# ARC-S-MCU.net
KiCad netlist of a schematic drawn in Altium Designer
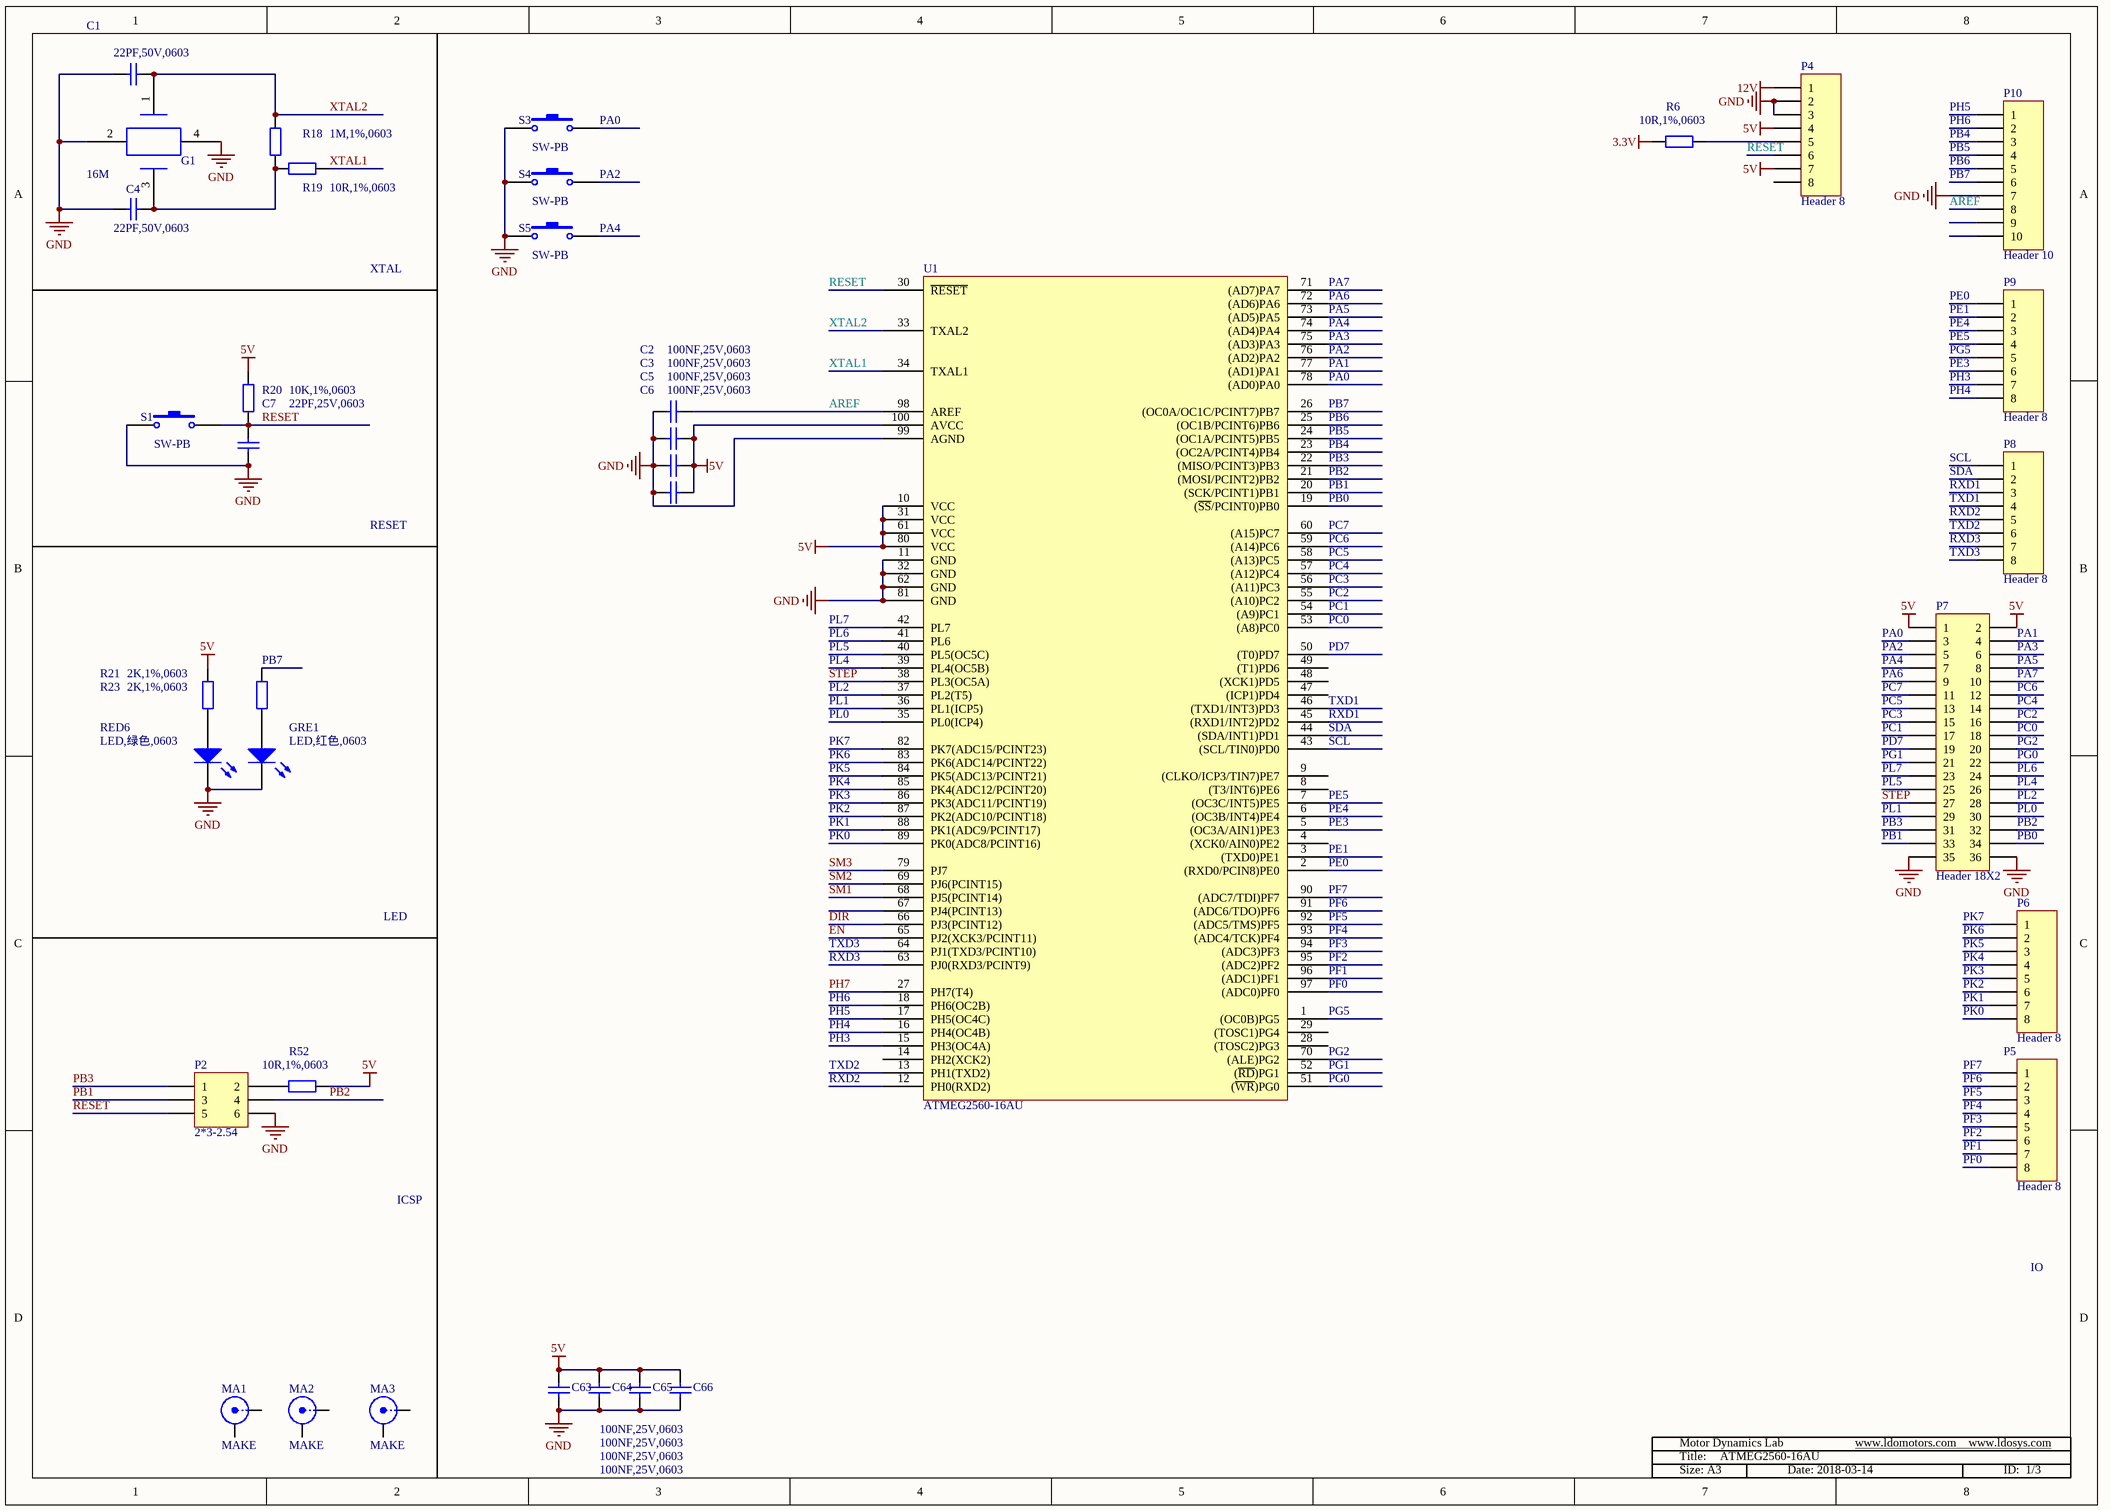
[diagram p0: ARC-S-MCU.SchDoc]

(export (version "E")
  (design (tool "Eeschema 10.0.6"))
  (components
    (comp (ref "C1")
      (value "22PF,50V,0603")
      (footprint "RC0603")
      (description "Capacitor")
      (fields (field (name "PUBLISHER") "Altium Limited"))
      (libsource (lib "Miscellaneous Devices") (part "Cap"))
    )
    (comp (ref "C2")
      (value "100NF,25V,0603")
      (footprint "RC0603")
      (description "Capacitor")
      (fields (field (name "PUBLISHER") "Altium Limited"))
      (libsource (lib "Miscellaneous Devices") (part "Cap"))
    )
    (comp (ref "C3")
      (value "100NF,25V,0603")
      (footprint "RC0603")
      (description "Capacitor")
      (fields (field (name "PUBLISHER") "Altium Limited"))
      (libsource (lib "Miscellaneous Devices") (part "Cap"))
    )
    (comp (ref "C4")
      (value "22PF,50V,0603")
      (footprint "RC0603")
      (description "Capacitor")
      (fields (field (name "PUBLISHER") "Altium Limited"))
      (libsource (lib "Miscellaneous Devices") (part "Cap"))
    )
    (comp (ref "C5")
      (value "100NF,25V,0603")
      (footprint "RC0603")
      (description "Capacitor")
      (fields (field (name "PUBLISHER") "Altium Limited"))
      (libsource (lib "Miscellaneous Devices") (part "Cap"))
    )
    (comp (ref "C6")
      (value "100NF,25V,0603")
      (footprint "RC0603")
      (description "Capacitor")
      (fields (field (name "PUBLISHER") "Altium Limited"))
      (libsource (lib "Miscellaneous Devices") (part "Cap"))
    )
    (comp (ref "C7")
      (value "22PF,25V,0603")
      (footprint "RC0603")
      (description "Capacitor")
      (fields (field (name "PUBLISHER") "Altium Limited"))
      (libsource (lib "Miscellaneous Devices") (part "Cap"))
    )
    (comp (ref "C63")
      (value "100NF,25V,0603")
      (footprint "RC0603")
      (description "Capacitor")
      (fields (field (name "PUBLISHER") "Altium Limited"))
      (libsource (lib "Miscellaneous Devices") (part "Cap"))
    )
    (comp (ref "C64")
      (value "100NF,25V,0603")
      (footprint "RC0603")
      (description "Capacitor")
      (fields (field (name "PUBLISHER") "Altium Limited"))
      (libsource (lib "Miscellaneous Devices") (part "Cap"))
    )
    (comp (ref "C65")
      (value "100NF,25V,0603")
      (footprint "RC0603")
      (description "Capacitor")
      (fields (field (name "PUBLISHER") "Altium Limited"))
      (libsource (lib "Miscellaneous Devices") (part "Cap"))
    )
    (comp (ref "C66")
      (value "100NF,25V,0603")
      (footprint "RC0603")
      (description "Capacitor")
      (fields (field (name "PUBLISHER") "Altium Limited"))
      (libsource (lib "Miscellaneous Devices") (part "Cap"))
    )
    (comp (ref "G1") (value "16M") (footprint "Y-3225") (libsource (lib "STM32F407VE") (part "G")))
    (comp (ref "GRE1")
      (value "LED,红色,0603")
      (footprint "LED-0603")
      (description "Typical INFRARED GaAs LED")
      (fields (field (name "PUBLISHER") "Altium Limited"))
      (libsource (lib "Miscellaneous Devices") (part "LED0"))
    )
    (comp (ref "MA1")
      (value "MAKE")
      (description "BNC Elbow Connector")
      (fields (field (name "PUBLISHER") "Altium Limited"))
      (libsource (lib "Miscellaneous Connectors") (part "BNC"))
    )
    (comp (ref "MA2")
      (value "MAKE")
      (description "BNC Elbow Connector")
      (fields (field (name "PUBLISHER") "Altium Limited"))
      (libsource (lib "Miscellaneous Connectors") (part "BNC"))
    )
    (comp (ref "MA3")
      (value "MAKE")
      (description "BNC Elbow Connector")
      (fields (field (name "PUBLISHER") "Altium Limited"))
      (libsource (lib "Miscellaneous Connectors") (part "BNC"))
    )
    (comp (ref "P2")
      (value "2*3-2.54")
      (footprint "HDR2X3")
      (description "Header, 3-Pin, Dual row")
      (fields (field (name "PUBLISHER") "Altium Limited"))
      (libsource (lib "Miscellaneous Connectors") (part "Header 3X2"))
    )
    (comp (ref "P4")
      (value "Header 8")
      (footprint "HDR1X8")
      (description "Header, 8-Pin")
      (fields (field (name "PUBLISHER") "Altium Limited"))
      (libsource (lib "Miscellaneous Connectors") (part "Header 8"))
    )
    (comp (ref "P5")
      (value "Header 8")
      (footprint "HDR1X8")
      (description "Header, 8-Pin")
      (fields (field (name "PUBLISHER") "Altium Limited"))
      (libsource (lib "Miscellaneous Connectors") (part "Header 8"))
    )
    (comp (ref "P6")
      (value "Header 8")
      (footprint "HDR1X8")
      (description "Header, 8-Pin")
      (fields (field (name "PUBLISHER") "Altium Limited"))
      (libsource (lib "Miscellaneous Connectors") (part "Header 8"))
    )
    (comp (ref "P7")
      (value "Header 18X2")
      (footprint "HDR2X18")
      (description "Header, 18-Pin, Dual row")
      (fields (field (name "PUBLISHER") "Altium Limited"))
      (libsource (lib "Miscellaneous Connectors") (part "Header 18X2"))
    )
    (comp (ref "P8")
      (value "Header 8")
      (footprint "HDR1X8")
      (description "Header, 8-Pin")
      (fields (field (name "PUBLISHER") "Altium Limited"))
      (libsource (lib "Miscellaneous Connectors") (part "Header 8"))
    )
    (comp (ref "P9")
      (value "Header 8")
      (footprint "HDR1X8")
      (description "Header, 8-Pin")
      (fields (field (name "PUBLISHER") "Altium Limited"))
      (libsource (lib "Miscellaneous Connectors") (part "Header 8"))
    )
    (comp (ref "P10")
      (value "Header 10")
      (footprint "HDR1X10")
      (description "Header, 10-Pin")
      (fields (field (name "PUBLISHER") "Altium Limited"))
      (libsource (lib "Miscellaneous Connectors") (part "Header 10"))
    )
    (comp (ref "R6")
      (value "10R,1%,0603")
      (footprint "RC0603")
      (description "Resistor")
      (fields (field (name "PUBLISHER") "Altium Limited"))
      (libsource (lib "") (part "Res2_2"))
    )
    (comp (ref "R18")
      (value "1M,1%,0603")
      (footprint "RC0603")
      (description "Resistor")
      (fields (field (name "PUBLISHER") "Altium Limited"))
      (libsource (lib "") (part "Res2_1"))
    )
    (comp (ref "R19")
      (value "10R,1%,0603")
      (footprint "RC0603")
      (description "Resistor")
      (fields (field (name "PUBLISHER") "Altium Limited"))
      (libsource (lib "Miscellaneous Devices") (part "Res2"))
    )
    (comp (ref "R20")
      (value "10K,1%,0603")
      (footprint "RC0603")
      (description "Resistor")
      (fields (field (name "PUBLISHER") "Altium Limited"))
      (libsource (lib "") (part "Res2_1"))
    )
    (comp (ref "R21")
      (value "2K,1%,0603")
      (footprint "RC0603")
      (description "Resistor")
      (fields (field (name "PUBLISHER") "Altium Limited"))
      (libsource (lib "") (part "Res2_1"))
    )
    (comp (ref "R23")
      (value "2K,1%,0603")
      (footprint "RC0603")
      (description "Resistor")
      (fields (field (name "PUBLISHER") "Altium Limited"))
      (libsource (lib "") (part "Res2_1"))
    )
    (comp (ref "R52")
      (value "10R,1%,0603")
      (footprint "RC0603")
      (description "Resistor")
      (fields (field (name "PUBLISHER") "Altium Limited"))
      (libsource (lib "") (part "Res2_2"))
    )
    (comp (ref "RED6")
      (value "LED,绿色,0603")
      (footprint "LED-0603")
      (description "Typical INFRARED GaAs LED")
      (fields (field (name "PUBLISHER") "Altium Limited"))
      (libsource (lib "Miscellaneous Devices") (part "LED0"))
    )
    (comp (ref "S1")
      (value "SW-PB")
      (footprint "DIP6*6")
      (description "Switch")
      (fields (field (name "PUBLISHER") "Altium Limited"))
      (libsource (lib "Miscellaneous Devices") (part "SW-PB"))
    )
    (comp (ref "S3")
      (value "SW-PB")
      (footprint "DIP6*6")
      (description "Switch")
      (fields (field (name "PUBLISHER") "Altium Limited"))
      (libsource (lib "Miscellaneous Devices") (part "SW-PB"))
    )
    (comp (ref "S4")
      (value "SW-PB")
      (footprint "DIP6*6")
      (description "Switch")
      (fields (field (name "PUBLISHER") "Altium Limited"))
      (libsource (lib "Miscellaneous Devices") (part "SW-PB"))
    )
    (comp (ref "S5")
      (value "SW-PB")
      (footprint "DIP6*6")
      (description "Switch")
      (fields (field (name "PUBLISHER") "Altium Limited"))
      (libsource (lib "Miscellaneous Devices") (part "SW-PB"))
    )
    (comp (ref "U1")
      (value "ATMEG2560-16AU")
      (footprint "LQFP-100")
      (libsource (lib "LDO原理图库") (part "ATMEG2560-16AU"))
    )
  )
  (nets
    (net (code "1") (name "/AREF") (class "Default")
      (node (ref "C2") (pin "1") (pinfunction "1_1") (pintype "passive"))
      (node (ref "P10") (pin "8") (pinfunction "8_8") (pintype "passive"))
      (node (ref "U1") (pin "98") (pinfunction "AREF_98") (pintype "passive"))
    )
    (net (code "2") (name "/DIR") (class "Default")
      (node (ref "U1") (pin "66") (pinfunction "PJ3(PCINT12)_66") (pintype "passive"))
    )
    (net (code "3") (name "/EN") (class "Default")
      (node (ref "U1") (pin "65") (pinfunction "PJ2(XCK3/PCINT11)_65") (pintype "passive"))
    )
    (net (code "4") (name "/PA0") (class "Default")
      (node (ref "P7") (pin "3") (pinfunction "3_3") (pintype "passive"))
      (node (ref "S3") (pin "2") (pinfunction "2_2") (pintype "passive"))
      (node (ref "U1") (pin "78") (pinfunction "(AD0)PA0_78") (pintype "passive"))
    )
    (net (code "5") (name "/PA1") (class "Default")
      (node (ref "P7") (pin "4") (pinfunction "4_4") (pintype "passive"))
      (node (ref "U1") (pin "77") (pinfunction "(AD1)PA1_77") (pintype "passive"))
    )
    (net (code "6") (name "/PA2") (class "Default")
      (node (ref "P7") (pin "5") (pinfunction "5_5") (pintype "passive"))
      (node (ref "S4") (pin "2") (pinfunction "2_2") (pintype "passive"))
      (node (ref "U1") (pin "76") (pinfunction "(AD2)PA2_76") (pintype "passive"))
    )
    (net (code "7") (name "/PA3") (class "Default")
      (node (ref "P7") (pin "6") (pinfunction "6_6") (pintype "passive"))
      (node (ref "U1") (pin "75") (pinfunction "(AD3)PA3_75") (pintype "passive"))
    )
    (net (code "8") (name "/PA4") (class "Default")
      (node (ref "P7") (pin "7") (pinfunction "7_7") (pintype "passive"))
      (node (ref "S5") (pin "2") (pinfunction "2_2") (pintype "passive"))
      (node (ref "U1") (pin "74") (pinfunction "(AD4)PA4_74") (pintype "passive"))
    )
    (net (code "9") (name "/PA5") (class "Default")
      (node (ref "P7") (pin "8") (pinfunction "8_8") (pintype "passive"))
      (node (ref "U1") (pin "73") (pinfunction "(AD5)PA5_73") (pintype "passive"))
    )
    (net (code "10") (name "/PA6") (class "Default")
      (node (ref "P7") (pin "9") (pinfunction "9_9") (pintype "passive"))
      (node (ref "U1") (pin "72") (pinfunction "(AD6)PA6_72") (pintype "passive"))
    )
    (net (code "11") (name "/PA7") (class "Default")
      (node (ref "P7") (pin "10") (pinfunction "10_10") (pintype "passive"))
      (node (ref "U1") (pin "71") (pinfunction "(AD7)PA7_71") (pintype "passive"))
    )
    (net (code "12") (name "/PB0") (class "Default")
      (node (ref "P7") (pin "34") (pinfunction "34_34") (pintype "passive"))
      (node (ref "U1") (pin "19") (pinfunction "(~{SS}/PCINT0)PB0_19") (pintype "passive"))
    )
    (net (code "13") (name "/PB1") (class "Default")
      (node (ref "P2") (pin "3") (pinfunction "3_3") (pintype "passive"))
      (node (ref "P7") (pin "33") (pinfunction "33_33") (pintype "passive"))
      (node (ref "U1") (pin "20") (pinfunction "(SCK/PCINT1)PB1_20") (pintype "passive"))
    )
    (net (code "14") (name "/PB2") (class "Default")
      (node (ref "P2") (pin "4") (pinfunction "4_4") (pintype "passive"))
      (node (ref "P7") (pin "32") (pinfunction "32_32") (pintype "passive"))
      (node (ref "U1") (pin "21") (pinfunction "(MOSI/PCINT2)PB2_21") (pintype "passive"))
    )
    (net (code "15") (name "/PB3") (class "Default")
      (node (ref "P2") (pin "1") (pinfunction "1_1") (pintype "passive"))
      (node (ref "P7") (pin "31") (pinfunction "31_31") (pintype "passive"))
      (node (ref "U1") (pin "22") (pinfunction "(MISO/PCINT3)PB3_22") (pintype "passive"))
    )
    (net (code "16") (name "/PB4") (class "Default")
      (node (ref "P10") (pin "3") (pinfunction "3_3") (pintype "passive"))
      (node (ref "U1") (pin "23") (pinfunction "(OC2A/PCINT4)PB4_23") (pintype "passive"))
    )
    (net (code "17") (name "/PB5") (class "Default")
      (node (ref "P10") (pin "4") (pinfunction "4_4") (pintype "passive"))
      (node (ref "U1") (pin "24") (pinfunction "(OC1A/PCINT5)PB5_24") (pintype "passive"))
    )
    (net (code "18") (name "/PB6") (class "Default")
      (node (ref "P10") (pin "5") (pinfunction "5_5") (pintype "passive"))
      (node (ref "U1") (pin "25") (pinfunction "(OC1B/PCINT6)PB6_25") (pintype "passive"))
    )
    (net (code "19") (name "/PB7") (class "Default")
      (node (ref "P10") (pin "6") (pinfunction "6_6") (pintype "passive"))
      (node (ref "R21") (pin "1") (pinfunction "1_1") (pintype "passive"))
      (node (ref "U1") (pin "26") (pinfunction "(OC0A/OC1C/PCINT7)PB7_26") (pintype "passive"))
    )
    (net (code "20") (name "/PC0") (class "Default")
      (node (ref "P7") (pin "18") (pinfunction "18_18") (pintype "passive"))
      (node (ref "U1") (pin "53") (pinfunction "(A8)PC0_53") (pintype "passive"))
    )
    (net (code "21") (name "/PC1") (class "Default")
      (node (ref "P7") (pin "17") (pinfunction "17_17") (pintype "passive"))
      (node (ref "U1") (pin "54") (pinfunction "(A9)PC1_54") (pintype "passive"))
    )
    (net (code "22") (name "/PC2") (class "Default")
      (node (ref "P7") (pin "16") (pinfunction "16_16") (pintype "passive"))
      (node (ref "U1") (pin "55") (pinfunction "(A10)PC2_55") (pintype "passive"))
    )
    (net (code "23") (name "/PC3") (class "Default")
      (node (ref "P7") (pin "15") (pinfunction "15_15") (pintype "passive"))
      (node (ref "U1") (pin "56") (pinfunction "(A11)PC3_56") (pintype "passive"))
    )
    (net (code "24") (name "/PC4") (class "Default")
      (node (ref "P7") (pin "14") (pinfunction "14_14") (pintype "passive"))
      (node (ref "U1") (pin "57") (pinfunction "(A12)PC4_57") (pintype "passive"))
    )
    (net (code "25") (name "/PC5") (class "Default")
      (node (ref "P7") (pin "13") (pinfunction "13_13") (pintype "passive"))
      (node (ref "U1") (pin "58") (pinfunction "(A13)PC5_58") (pintype "passive"))
    )
    (net (code "26") (name "/PC6") (class "Default")
      (node (ref "P7") (pin "12") (pinfunction "12_12") (pintype "passive"))
      (node (ref "U1") (pin "59") (pinfunction "(A14)PC6_59") (pintype "passive"))
    )
    (net (code "27") (name "/PC7") (class "Default")
      (node (ref "P7") (pin "11") (pinfunction "11_11") (pintype "passive"))
      (node (ref "U1") (pin "60") (pinfunction "(A15)PC7_60") (pintype "passive"))
    )
    (net (code "28") (name "/PD7") (class "Default")
      (node (ref "P7") (pin "19") (pinfunction "19_19") (pintype "passive"))
      (node (ref "U1") (pin "50") (pinfunction "(T0)PD7_50") (pintype "passive"))
    )
    (net (code "29") (name "/PE0") (class "Default")
      (node (ref "P9") (pin "1") (pinfunction "1_1") (pintype "passive"))
      (node (ref "U1") (pin "2") (pinfunction "(RXD0/PCIN8)PE0_2") (pintype "passive"))
    )
    (net (code "30") (name "/PE1") (class "Default")
      (node (ref "P9") (pin "2") (pinfunction "2_2") (pintype "passive"))
      (node (ref "U1") (pin "3") (pinfunction "(TXD0)PE1_3") (pintype "passive"))
    )
    (net (code "31") (name "/PE3") (class "Default")
      (node (ref "P9") (pin "6") (pinfunction "6_6") (pintype "passive"))
      (node (ref "U1") (pin "5") (pinfunction "(OC3A/AIN1)PE3_5") (pintype "passive"))
    )
    (net (code "32") (name "/PE4") (class "Default")
      (node (ref "P9") (pin "3") (pinfunction "3_3") (pintype "passive"))
      (node (ref "U1") (pin "6") (pinfunction "(OC3B/INT4)PE4_6") (pintype "passive"))
    )
    (net (code "33") (name "/PE5") (class "Default")
      (node (ref "P9") (pin "4") (pinfunction "4_4") (pintype "passive"))
      (node (ref "U1") (pin "7") (pinfunction "(OC3C/INT5)PE5_7") (pintype "passive"))
    )
    (net (code "34") (name "/PF0") (class "Default")
      (node (ref "P5") (pin "8") (pinfunction "8_8") (pintype "passive"))
      (node (ref "U1") (pin "97") (pinfunction "(ADC0)PF0_97") (pintype "passive"))
    )
    (net (code "35") (name "/PF1") (class "Default")
      (node (ref "P5") (pin "7") (pinfunction "7_7") (pintype "passive"))
      (node (ref "U1") (pin "96") (pinfunction "(ADC1)PF1_96") (pintype "passive"))
    )
    (net (code "36") (name "/PF2") (class "Default")
      (node (ref "P5") (pin "6") (pinfunction "6_6") (pintype "passive"))
      (node (ref "U1") (pin "95") (pinfunction "(ADC2)PF2_95") (pintype "passive"))
    )
    (net (code "37") (name "/PF3") (class "Default")
      (node (ref "P5") (pin "5") (pinfunction "5_5") (pintype "passive"))
      (node (ref "U1") (pin "94") (pinfunction "(ADC3)PF3_94") (pintype "passive"))
    )
    (net (code "38") (name "/PF4") (class "Default")
      (node (ref "P5") (pin "4") (pinfunction "4_4") (pintype "passive"))
      (node (ref "U1") (pin "93") (pinfunction "(ADC4/TCK)PF4_93") (pintype "passive"))
    )
    (net (code "39") (name "/PF5") (class "Default")
      (node (ref "P5") (pin "3") (pinfunction "3_3") (pintype "passive"))
      (node (ref "U1") (pin "92") (pinfunction "(ADC5/TMS)PF5_92") (pintype "passive"))
    )
    (net (code "40") (name "/PF6") (class "Default")
      (node (ref "P5") (pin "2") (pinfunction "2_2") (pintype "passive"))
      (node (ref "U1") (pin "91") (pinfunction "(ADC6/TDO)PF6_91") (pintype "passive"))
    )
    (net (code "41") (name "/PF7") (class "Default")
      (node (ref "P5") (pin "1") (pinfunction "1_1") (pintype "passive"))
      (node (ref "U1") (pin "90") (pinfunction "(ADC7/TDI)PF7_90") (pintype "passive"))
    )
    (net (code "42") (name "/PG0") (class "Default")
      (node (ref "P7") (pin "22") (pinfunction "22_22") (pintype "passive"))
      (node (ref "U1") (pin "51") (pinfunction "(~{WR})PG0_51") (pintype "passive"))
    )
    (net (code "43") (name "/PG1") (class "Default")
      (node (ref "P7") (pin "21") (pinfunction "21_21") (pintype "passive"))
      (node (ref "U1") (pin "52") (pinfunction "(~{RD})PG1_52") (pintype "passive"))
    )
    (net (code "44") (name "/PG2") (class "Default")
      (node (ref "P7") (pin "20") (pinfunction "20_20") (pintype "passive"))
      (node (ref "U1") (pin "70") (pinfunction "(ALE)PG2_70") (pintype "passive"))
    )
    (net (code "45") (name "/PG5") (class "Default")
      (node (ref "P9") (pin "5") (pinfunction "5_5") (pintype "passive"))
      (node (ref "U1") (pin "1") (pinfunction "(OC0B)PG5_1") (pintype "passive"))
    )
    (net (code "46") (name "/PH3") (class "Default")
      (node (ref "P9") (pin "7") (pinfunction "7_7") (pintype "passive"))
      (node (ref "U1") (pin "15") (pinfunction "PH3(OC4A)_15") (pintype "passive"))
    )
    (net (code "47") (name "/PH4") (class "Default")
      (node (ref "P9") (pin "8") (pinfunction "8_8") (pintype "passive"))
      (node (ref "U1") (pin "16") (pinfunction "PH4(OC4B)_16") (pintype "passive"))
    )
    (net (code "48") (name "/PH5") (class "Default")
      (node (ref "P10") (pin "1") (pinfunction "1_1") (pintype "passive"))
      (node (ref "U1") (pin "17") (pinfunction "PH5(OC4C)_17") (pintype "passive"))
    )
    (net (code "49") (name "/PH6") (class "Default")
      (node (ref "P10") (pin "2") (pinfunction "2_2") (pintype "passive"))
      (node (ref "U1") (pin "18") (pinfunction "PH6(OC2B)_18") (pintype "passive"))
    )
    (net (code "50") (name "/PH7") (class "Default")
      (node (ref "U1") (pin "27") (pinfunction "PH7(T4)_27") (pintype "passive"))
    )
    (net (code "51") (name "/PK0") (class "Default")
      (node (ref "P6") (pin "8") (pinfunction "8_8") (pintype "passive"))
      (node (ref "U1") (pin "89") (pinfunction "PK0(ADC8/PCINT16)_89") (pintype "passive"))
    )
    (net (code "52") (name "/PK1") (class "Default")
      (node (ref "P6") (pin "7") (pinfunction "7_7") (pintype "passive"))
      (node (ref "U1") (pin "88") (pinfunction "PK1(ADC9/PCINT17)_88") (pintype "passive"))
    )
    (net (code "53") (name "/PK2") (class "Default")
      (node (ref "P6") (pin "6") (pinfunction "6_6") (pintype "passive"))
      (node (ref "U1") (pin "87") (pinfunction "PK2(ADC10/PCINT18)_87") (pintype "passive"))
    )
    (net (code "54") (name "/PK3") (class "Default")
      (node (ref "P6") (pin "5") (pinfunction "5_5") (pintype "passive"))
      (node (ref "U1") (pin "86") (pinfunction "PK3(ADC11/PCINT19)_86") (pintype "passive"))
    )
    (net (code "55") (name "/PK4") (class "Default")
      (node (ref "P6") (pin "4") (pinfunction "4_4") (pintype "passive"))
      (node (ref "U1") (pin "85") (pinfunction "PK4(ADC12/PCINT20)_85") (pintype "passive"))
    )
    (net (code "56") (name "/PK5") (class "Default")
      (node (ref "P6") (pin "3") (pinfunction "3_3") (pintype "passive"))
      (node (ref "U1") (pin "84") (pinfunction "PK5(ADC13/PCINT21)_84") (pintype "passive"))
    )
    (net (code "57") (name "/PK6") (class "Default")
      (node (ref "P6") (pin "2") (pinfunction "2_2") (pintype "passive"))
      (node (ref "U1") (pin "83") (pinfunction "PK6(ADC14/PCINT22)_83") (pintype "passive"))
    )
    (net (code "58") (name "/PK7") (class "Default")
      (node (ref "P6") (pin "1") (pinfunction "1_1") (pintype "passive"))
      (node (ref "U1") (pin "82") (pinfunction "PK7(ADC15/PCINT23)_82") (pintype "passive"))
    )
    (net (code "59") (name "/PL0") (class "Default")
      (node (ref "P7") (pin "30") (pinfunction "30_30") (pintype "passive"))
      (node (ref "U1") (pin "35") (pinfunction "PL0(ICP4)_35") (pintype "passive"))
    )
    (net (code "60") (name "/PL1") (class "Default")
      (node (ref "P7") (pin "29") (pinfunction "29_29") (pintype "passive"))
      (node (ref "U1") (pin "36") (pinfunction "PL1(ICP5)_36") (pintype "passive"))
    )
    (net (code "61") (name "/PL2") (class "Default")
      (node (ref "P7") (pin "28") (pinfunction "28_28") (pintype "passive"))
      (node (ref "U1") (pin "37") (pinfunction "PL2(T5)_37") (pintype "passive"))
    )
    (net (code "62") (name "/PL4") (class "Default")
      (node (ref "P7") (pin "26") (pinfunction "26_26") (pintype "passive"))
      (node (ref "U1") (pin "39") (pinfunction "PL4(OC5B)_39") (pintype "passive"))
    )
    (net (code "63") (name "/PL5") (class "Default")
      (node (ref "P7") (pin "25") (pinfunction "25_25") (pintype "passive"))
      (node (ref "U1") (pin "40") (pinfunction "PL5(OC5C)_40") (pintype "passive"))
    )
    (net (code "64") (name "/PL6") (class "Default")
      (node (ref "P7") (pin "24") (pinfunction "24_24") (pintype "passive"))
      (node (ref "U1") (pin "41") (pinfunction "PL6_41") (pintype "passive"))
    )
    (net (code "65") (name "/PL7") (class "Default")
      (node (ref "P7") (pin "23") (pinfunction "23_23") (pintype "passive"))
      (node (ref "U1") (pin "42") (pinfunction "PL7_42") (pintype "passive"))
    )
    (net (code "66") (name "/RESET") (class "Default")
      (node (ref "C7") (pin "1") (pinfunction "1_1") (pintype "passive"))
      (node (ref "P2") (pin "5") (pinfunction "5_5") (pintype "passive"))
      (node (ref "P4") (pin "6") (pinfunction "6_6") (pintype "passive"))
      (node (ref "R20") (pin "2") (pinfunction "2_2") (pintype "passive"))
      (node (ref "S1") (pin "2") (pinfunction "2_2") (pintype "passive"))
      (node (ref "U1") (pin "30") (pinfunction "~{RESET}_30") (pintype "passive"))
    )
    (net (code "67") (name "/RXD1") (class "Default")
      (node (ref "P8") (pin "3") (pinfunction "3_3") (pintype "passive"))
      (node (ref "U1") (pin "45") (pinfunction "(RXD1/INT2)PD2_45") (pintype "passive"))
    )
    (net (code "68") (name "/RXD2") (class "Default")
      (node (ref "P8") (pin "5") (pinfunction "5_5") (pintype "passive"))
      (node (ref "U1") (pin "12") (pinfunction "PH0(RXD2)_12") (pintype "passive"))
    )
    (net (code "69") (name "/RXD3") (class "Default")
      (node (ref "P8") (pin "7") (pinfunction "7_7") (pintype "passive"))
      (node (ref "U1") (pin "63") (pinfunction "PJ0(RXD3/PCINT9)_63") (pintype "passive"))
    )
    (net (code "70") (name "/SCL") (class "Default")
      (node (ref "P8") (pin "1") (pinfunction "1_1") (pintype "passive"))
      (node (ref "U1") (pin "43") (pinfunction "(SCL/TIN0)PD0_43") (pintype "passive"))
    )
    (net (code "71") (name "/SDA") (class "Default")
      (node (ref "P8") (pin "2") (pinfunction "2_2") (pintype "passive"))
      (node (ref "U1") (pin "44") (pinfunction "(SDA/INT1)PD1_44") (pintype "passive"))
    )
    (net (code "72") (name "/SM1") (class "Default")
      (node (ref "U1") (pin "68") (pinfunction "PJ5(PCINT14)_68") (pintype "passive"))
    )
    (net (code "73") (name "/SM2") (class "Default")
      (node (ref "U1") (pin "69") (pinfunction "PJ6(PCINT15)_69") (pintype "passive"))
    )
    (net (code "74") (name "/SM3") (class "Default")
      (node (ref "U1") (pin "79") (pinfunction "PJ7_79") (pintype "passive"))
    )
    (net (code "75") (name "/STEP") (class "Default")
      (node (ref "P7") (pin "27") (pinfunction "27_27") (pintype "passive"))
      (node (ref "U1") (pin "38") (pinfunction "PL3(OC5A)_38") (pintype "passive"))
    )
    (net (code "76") (name "/TXD1") (class "Default")
      (node (ref "P8") (pin "4") (pinfunction "4_4") (pintype "passive"))
      (node (ref "U1") (pin "46") (pinfunction "(TXD1/INT3)PD3_46") (pintype "passive"))
    )
    (net (code "77") (name "/TXD2") (class "Default")
      (node (ref "P8") (pin "6") (pinfunction "6_6") (pintype "passive"))
      (node (ref "U1") (pin "13") (pinfunction "PH1(TXD2)_13") (pintype "passive"))
    )
    (net (code "78") (name "/TXD3") (class "Default")
      (node (ref "P8") (pin "8") (pinfunction "8_8") (pintype "passive"))
      (node (ref "U1") (pin "64") (pinfunction "PJ1(TXD3/PCINT10)_64") (pintype "passive"))
    )
    (net (code "79") (name "/XTAL1") (class "Default")
      (node (ref "R19") (pin "2") (pinfunction "2_2") (pintype "passive"))
      (node (ref "U1") (pin "34") (pinfunction "TXAL1_34") (pintype "passive"))
    )
    (net (code "80") (name "/XTAL2") (class "Default")
      (node (ref "C1") (pin "1") (pinfunction "1_1") (pintype "passive"))
      (node (ref "G1") (pin "1") (pintype "passive"))
      (node (ref "R18") (pin "1") (pinfunction "1_1") (pintype "passive"))
      (node (ref "U1") (pin "33") (pinfunction "TXAL2_33") (pintype "passive"))
    )
    (net (code "81") (name "3.3V") (class "Default")
      (node (ref "R6") (pin "2") (pinfunction "2_2") (pintype "passive"))
    )
    (net (code "82") (name "5V") (class "Default")
      (node (ref "C3") (pin "1") (pinfunction "1_1") (pintype "passive"))
      (node (ref "C5") (pin "1") (pinfunction "1_1") (pintype "passive"))
      (node (ref "C6") (pin "1") (pinfunction "1_1") (pintype "passive"))
      (node (ref "C63") (pin "1") (pinfunction "1_1") (pintype "passive"))
      (node (ref "C64") (pin "1") (pinfunction "1_1") (pintype "passive"))
      (node (ref "C65") (pin "1") (pinfunction "1_1") (pintype "passive"))
      (node (ref "C66") (pin "1") (pinfunction "1_1") (pintype "passive"))
      (node (ref "P4") (pin "4") (pinfunction "4_4") (pintype "passive"))
      (node (ref "P4") (pin "7") (pinfunction "7_7") (pintype "passive"))
      (node (ref "P7") (pin "1") (pinfunction "1_1") (pintype "passive"))
      (node (ref "P7") (pin "2") (pinfunction "2_2") (pintype "passive"))
      (node (ref "R20") (pin "1") (pinfunction "1_1") (pintype "passive"))
      (node (ref "R23") (pin "1") (pinfunction "1_1") (pintype "passive"))
      (node (ref "R52") (pin "1") (pinfunction "1_1") (pintype "passive"))
      (node (ref "U1") (pin "10") (pinfunction "VCC_10") (pintype "passive"))
      (node (ref "U1") (pin "100") (pinfunction "AVCC_100") (pintype "passive"))
      (node (ref "U1") (pin "31") (pinfunction "VCC_31") (pintype "passive"))
      (node (ref "U1") (pin "61") (pinfunction "VCC_61") (pintype "passive"))
      (node (ref "U1") (pin "80") (pinfunction "VCC_80") (pintype "passive"))
    )
    (net (code "83") (name "12V") (class "Default")
      (node (ref "P4") (pin "1") (pinfunction "1_1") (pintype "passive"))
    )
    (net (code "84") (name "GND") (class "Default")
      (node (ref "C1") (pin "2") (pinfunction "2_2") (pintype "passive"))
      (node (ref "C2") (pin "2") (pinfunction "2_2") (pintype "passive"))
      (node (ref "C3") (pin "2") (pinfunction "2_2") (pintype "passive"))
      (node (ref "C4") (pin "1") (pinfunction "1_1") (pintype "passive"))
      (node (ref "C5") (pin "2") (pinfunction "2_2") (pintype "passive"))
      (node (ref "C6") (pin "2") (pinfunction "2_2") (pintype "passive"))
      (node (ref "C63") (pin "2") (pinfunction "2_2") (pintype "passive"))
      (node (ref "C64") (pin "2") (pinfunction "2_2") (pintype "passive"))
      (node (ref "C65") (pin "2") (pinfunction "2_2") (pintype "passive"))
      (node (ref "C66") (pin "2") (pinfunction "2_2") (pintype "passive"))
      (node (ref "C7") (pin "2") (pinfunction "2_2") (pintype "passive"))
      (node (ref "G1") (pin "2") (pintype "passive"))
      (node (ref "G1") (pin "4") (pintype "passive"))
      (node (ref "GRE1") (pin "2") (pinfunction "K_2") (pintype "passive"))
      (node (ref "P10") (pin "7") (pinfunction "7_7") (pintype "passive"))
      (node (ref "P2") (pin "6") (pinfunction "6_6") (pintype "passive"))
      (node (ref "P4") (pin "2") (pinfunction "2_2") (pintype "passive"))
      (node (ref "P4") (pin "3") (pinfunction "3_3") (pintype "passive"))
      (node (ref "P7") (pin "35") (pinfunction "35_35") (pintype "passive"))
      (node (ref "P7") (pin "36") (pinfunction "36_36") (pintype "passive"))
      (node (ref "RED6") (pin "2") (pinfunction "K_2") (pintype "passive"))
      (node (ref "S1") (pin "1") (pinfunction "1_1") (pintype "passive"))
      (node (ref "S3") (pin "1") (pinfunction "1_1") (pintype "passive"))
      (node (ref "S4") (pin "1") (pinfunction "1_1") (pintype "passive"))
      (node (ref "S5") (pin "1") (pinfunction "1_1") (pintype "passive"))
      (node (ref "U1") (pin "11") (pinfunction "GND_11") (pintype "passive"))
      (node (ref "U1") (pin "32") (pinfunction "GND_32") (pintype "passive"))
      (node (ref "U1") (pin "62") (pinfunction "GND_62") (pintype "passive"))
      (node (ref "U1") (pin "81") (pinfunction "GND_81") (pintype "passive"))
      (node (ref "U1") (pin "99") (pinfunction "AGND_99") (pintype "passive"))
    )
    (net (code "85") (name "Net-(C4-Pad2)") (class "Default")
      (node (ref "C4") (pin "2") (pinfunction "2_2") (pintype "passive"))
      (node (ref "G1") (pin "3") (pintype "passive"))
      (node (ref "R18") (pin "2") (pinfunction "2_2") (pintype "passive"))
      (node (ref "R19") (pin "1") (pinfunction "1_1") (pintype "passive"))
    )
    (net (code "86") (name "Net-(GRE1-A)") (class "Default")
      (node (ref "GRE1") (pin "1") (pinfunction "A_1") (pintype "passive"))
      (node (ref "R21") (pin "2") (pinfunction "2_2") (pintype "passive"))
    )
    (net (code "87") (name "Net-(P2-Pad2)") (class "Default")
      (node (ref "P2") (pin "2") (pinfunction "2_2") (pintype "passive"))
      (node (ref "R52") (pin "2") (pinfunction "2_2") (pintype "passive"))
    )
    (net (code "88") (name "Net-(P4-Pad5)") (class "Default")
      (node (ref "P4") (pin "5") (pinfunction "5_5") (pintype "passive"))
      (node (ref "R6") (pin "1") (pinfunction "1_1") (pintype "passive"))
    )
    (net (code "89") (name "Net-(RED6-A)") (class "Default")
      (node (ref "R23") (pin "2") (pinfunction "2_2") (pintype "passive"))
      (node (ref "RED6") (pin "1") (pinfunction "A_1") (pintype "passive"))
    )
    (net (code "90") (name "unconnected-(MA1-X-Pad1)") (class "Default")
      (node (ref "MA1") (pin "1") (pinfunction "X_1") (pintype "passive"))
    )
    (net (code "91") (name "unconnected-(MA1-Y-Pad2)") (class "Default")
      (node (ref "MA1") (pin "2") (pinfunction "Y_2") (pintype "passive"))
    )
    (net (code "92") (name "unconnected-(MA2-X-Pad1)") (class "Default")
      (node (ref "MA2") (pin "1") (pinfunction "X_1") (pintype "passive"))
    )
    (net (code "93") (name "unconnected-(MA2-Y-Pad2)") (class "Default")
      (node (ref "MA2") (pin "2") (pinfunction "Y_2") (pintype "passive"))
    )
    (net (code "94") (name "unconnected-(MA3-X-Pad1)") (class "Default")
      (node (ref "MA3") (pin "1") (pinfunction "X_1") (pintype "passive"))
    )
    (net (code "95") (name "unconnected-(MA3-Y-Pad2)") (class "Default")
      (node (ref "MA3") (pin "2") (pinfunction "Y_2") (pintype "passive"))
    )
    (net (code "96") (name "unconnected-(P4-Pad8)") (class "Default")
      (node (ref "P4") (pin "8") (pinfunction "8_8") (pintype "passive"))
    )
    (net (code "97") (name "unconnected-(P10-Pad9)") (class "Default")
      (node (ref "P10") (pin "9") (pinfunction "9_9") (pintype "passive"))
    )
    (net (code "98") (name "unconnected-(P10-Pad10)") (class "Default")
      (node (ref "P10") (pin "10") (pinfunction "10_10") (pintype "passive"))
    )
    (net (code "99") (name "unconnected-(U1-(CLKO{slash}ICP3{slash}TIN7)PE7-Pad9)") (class "Default")
      (node (ref "U1") (pin "9") (pinfunction "(CLKO/ICP3/TIN7)PE7_9") (pintype "passive"))
    )
    (net (code "100") (name "unconnected-(U1-(ICP1)PD4-Pad47)") (class "Default")
      (node (ref "U1") (pin "47") (pinfunction "(ICP1)PD4_47") (pintype "passive"))
    )
    (net (code "101") (name "unconnected-(U1-(T1)PD6-Pad49)") (class "Default")
      (node (ref "U1") (pin "49") (pinfunction "(T1)PD6_49") (pintype "passive"))
    )
    (net (code "102") (name "unconnected-(U1-(T3{slash}INT6)PE6-Pad8)") (class "Default")
      (node (ref "U1") (pin "8") (pinfunction "(T3/INT6)PE6_8") (pintype "passive"))
    )
    (net (code "103") (name "unconnected-(U1-(TOSC1)PG4-Pad29)") (class "Default")
      (node (ref "U1") (pin "29") (pinfunction "(TOSC1)PG4_29") (pintype "passive"))
    )
    (net (code "104") (name "unconnected-(U1-(TOSC2)PG3-Pad28)") (class "Default")
      (node (ref "U1") (pin "28") (pinfunction "(TOSC2)PG3_28") (pintype "passive"))
    )
    (net (code "105") (name "unconnected-(U1-(XCK0{slash}AIN0)PE2-Pad4)") (class "Default")
      (node (ref "U1") (pin "4") (pinfunction "(XCK0/AIN0)PE2_4") (pintype "passive"))
    )
    (net (code "106") (name "unconnected-(U1-(XCK1)PD5-Pad48)") (class "Default")
      (node (ref "U1") (pin "48") (pinfunction "(XCK1)PD5_48") (pintype "passive"))
    )
    (net (code "107") (name "unconnected-(U1-PH2(XCK2)-Pad14)") (class "Default")
      (node (ref "U1") (pin "14") (pinfunction "PH2(XCK2)_14") (pintype "passive"))
    )
    (net (code "108") (name "unconnected-(U1-PJ4(PCINT13)-Pad67)") (class "Default")
      (node (ref "U1") (pin "67") (pinfunction "PJ4(PCINT13)_67") (pintype "passive"))
    )
  )
)
